# sch.net
KiCad netlist of a schematic drawn in EAGLE
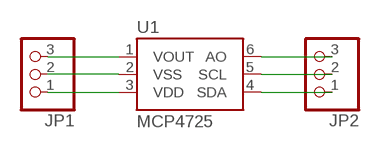
[diagram p0: schematic, sheet 1]

(export (version "E")
  (design (tool "Eeschema 10.0.6"))
  (components
    (comp (ref "JP1")
      (value "PINHD-1X3")
      (footprint "eagle-import:1X03")
      (libsource (lib "eagle-import") (part "PINHD-1X3"))
    )
    (comp (ref "JP2")
      (value "PINHD-1X3")
      (footprint "eagle-import:1X03")
      (libsource (lib "eagle-import") (part "PINHD-1X3"))
    )
    (comp (ref "U1")
      (value "MCP4725")
      (footprint "eagle-import:SOT23-6")
      (libsource (lib "eagle-import") (part "MCP4725SOT-23"))
    )
  )
  (nets
    (net (code "1") (name "Net-(U1-AO)") (class "Default")
      (node (ref "JP2") (pin "3") (pinfunction "3_3") (pintype "passive"))
      (node (ref "U1") (pin "6") (pinfunction "AO_6") (pintype "bidirectional"))
    )
    (net (code "2") (name "Net-(U1-SCL)") (class "Default")
      (node (ref "JP2") (pin "2") (pinfunction "2_2") (pintype "passive"))
      (node (ref "U1") (pin "5") (pinfunction "SCL_5") (pintype "bidirectional"))
    )
    (net (code "3") (name "Net-(U1-SDA)") (class "Default")
      (node (ref "JP2") (pin "1") (pinfunction "1_1") (pintype "passive"))
      (node (ref "U1") (pin "4") (pinfunction "SDA_4") (pintype "bidirectional"))
    )
    (net (code "4") (name "Net-(U1-VDD)") (class "Default")
      (node (ref "JP1") (pin "1") (pinfunction "1_1") (pintype "passive"))
      (node (ref "U1") (pin "3") (pinfunction "VDD_3") (pintype "bidirectional"))
    )
    (net (code "5") (name "Net-(U1-VOUT)") (class "Default")
      (node (ref "JP1") (pin "3") (pinfunction "3_3") (pintype "passive"))
      (node (ref "U1") (pin "1") (pinfunction "VOUT_1") (pintype "bidirectional"))
    )
    (net (code "6") (name "Net-(U1-VSS)") (class "Default")
      (node (ref "JP1") (pin "2") (pinfunction "2_2") (pintype "passive"))
      (node (ref "U1") (pin "2") (pinfunction "VSS_2") (pintype "bidirectional"))
    )
  )
)
